# Me-Line_Finder_v2_0.net
KiCad netlist of a schematic drawn in EAGLE
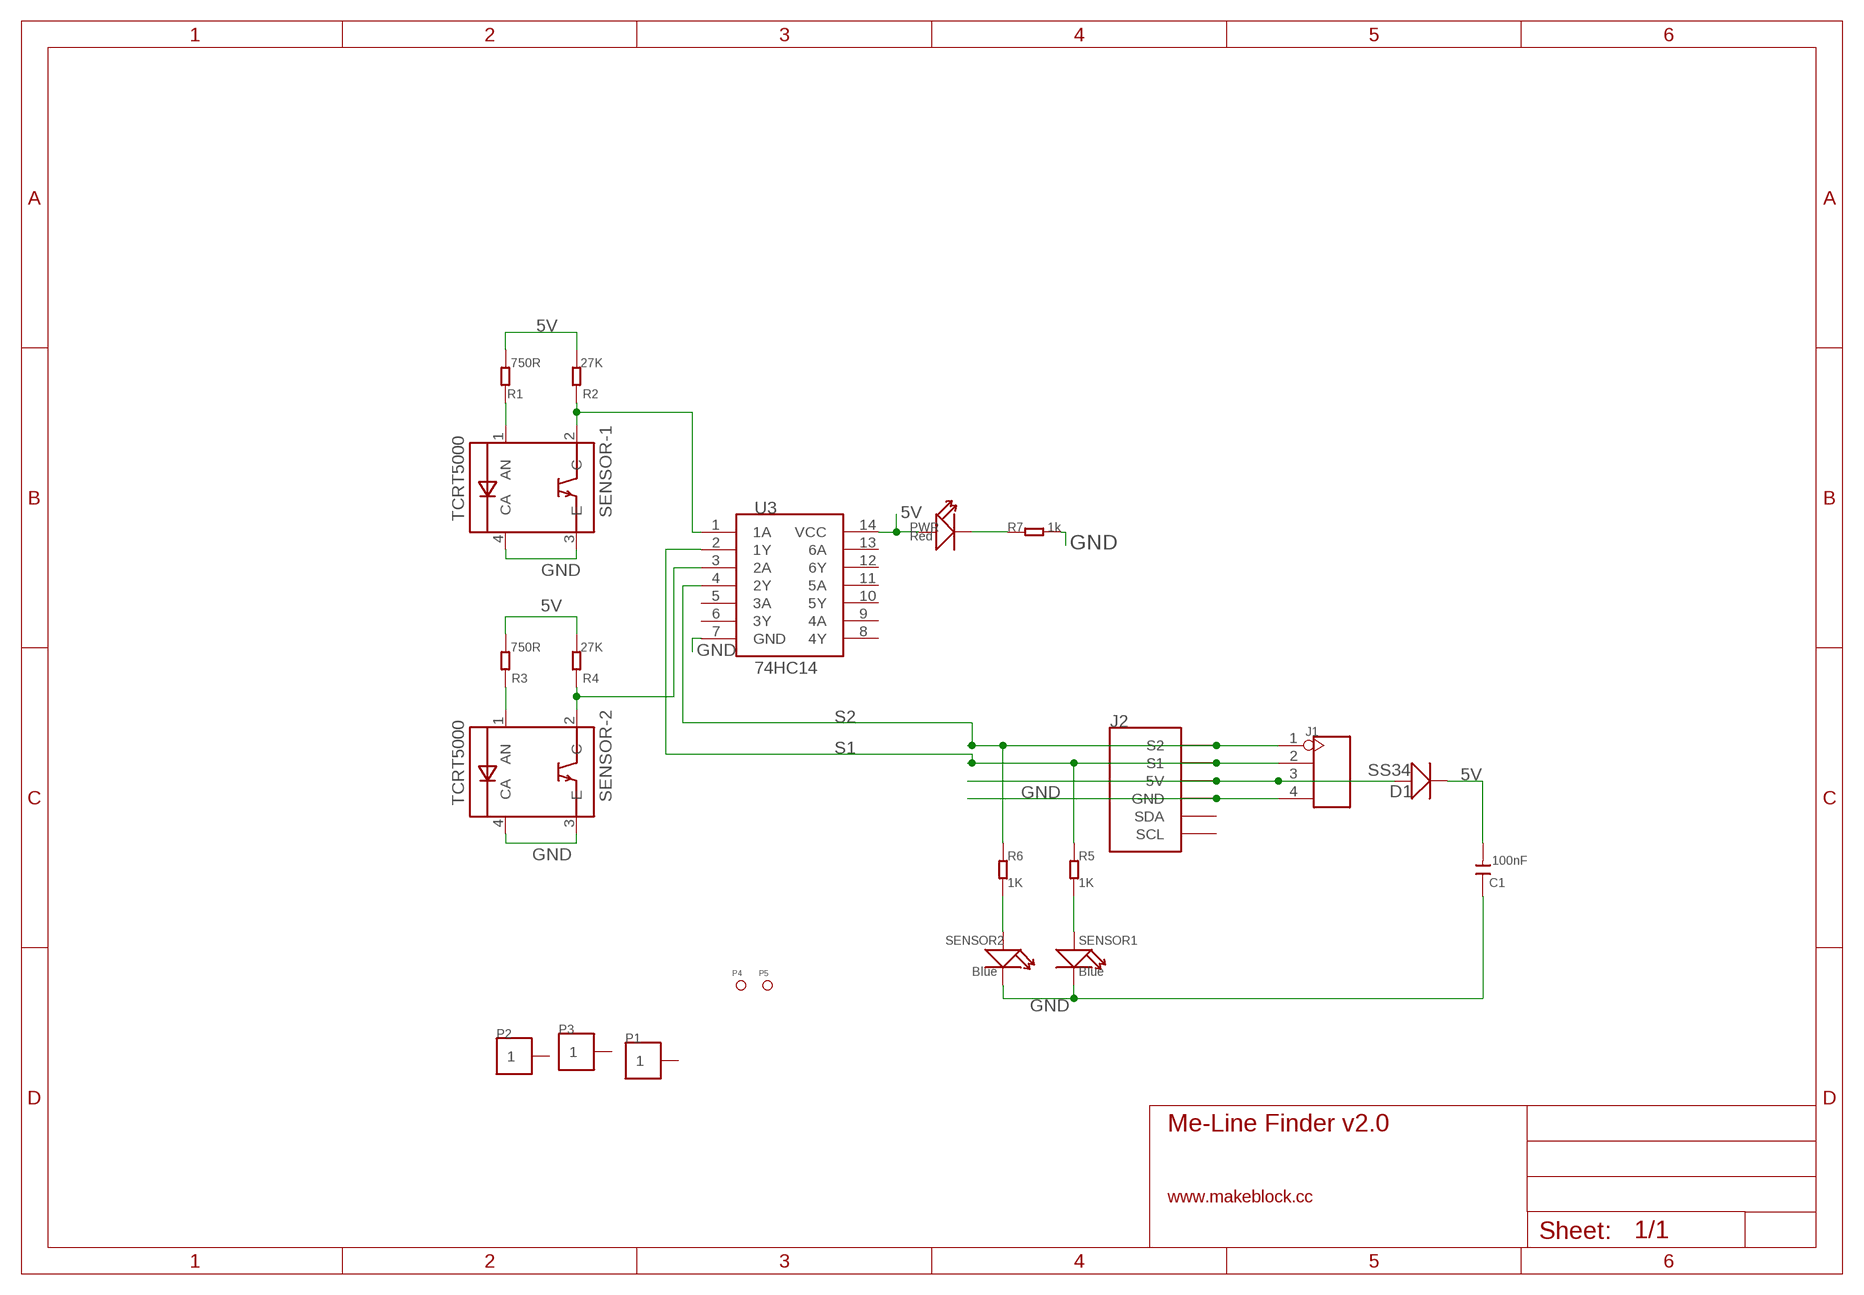
[diagram p0: schematic, sheet 1]

(export (version "E")
  (design (tool "Eeschema 10.0.6"))
  (components
    (comp (ref "C1")
      (value "100nF")
      (footprint "eagle-import:0603")
      (libsource (lib "eagle-import") (part "C-0603"))
    )
    (comp (ref "D1")
      (value "SS34")
      (footprint "eagle-import:D2010")
      (libsource (lib "eagle-import") (part "D'SMA'"))
    )
    (comp (ref "J1")
      (value "HEADER-4P-60/35MIL")
      (footprint "eagle-import:4P-65_35MIL")
      (libsource (lib "eagle-import") (part "HEADER-4P-60/35MIL"))
    )
    (comp (ref "J2")
      (value "RJ11-6P6C-DIGI")
      (footprint "eagle-import:RJ11-6P6C")
      (libsource (lib "eagle-import") (part "RJ11-6P6C-DIGI"))
    )
    (comp (ref "P1")
      (value "PAD-1P-4MM")
      (footprint "eagle-import:HOLE-01")
      (libsource (lib "eagle-import") (part "PAD-1P-4MM"))
    )
    (comp (ref "P2")
      (value "PAD-1P-4MM")
      (footprint "eagle-import:HOLE-01")
      (libsource (lib "eagle-import") (part "PAD-1P-4MM"))
    )
    (comp (ref "P3")
      (value "PAD-1P-4MM")
      (footprint "eagle-import:HOLE-01")
      (libsource (lib "eagle-import") (part "PAD-1P-4MM"))
    )
    (comp (ref "P4")
      (value "PAD-MARK")
      (footprint "eagle-import:ROUND-MARK-1.0")
      (fields (field (name "PARTNO") "DNP"))
      (libsource (lib "eagle-import") (part "PAD-MARK"))
    )
    (comp (ref "P5")
      (value "PAD-MARK")
      (footprint "eagle-import:ROUND-MARK-1.0")
      (fields (field (name "PARTNO") "DNP"))
      (libsource (lib "eagle-import") (part "PAD-MARK"))
    )
    (comp (ref "PWR")
      (value "Red")
      (footprint "eagle-import:LED-0603")
      (libsource (lib "eagle-import") (part "LED'0603'"))
    )
    (comp (ref "R1")
      (value "750R")
      (footprint "eagle-import:0603")
      (libsource (lib "eagle-import") (part "R-0603"))
    )
    (comp (ref "R2")
      (value "27K")
      (footprint "eagle-import:0603")
      (libsource (lib "eagle-import") (part "R-0603"))
    )
    (comp (ref "R3")
      (value "750R")
      (footprint "eagle-import:0603")
      (libsource (lib "eagle-import") (part "R-0603"))
    )
    (comp (ref "R4")
      (value "27K")
      (footprint "eagle-import:0603")
      (libsource (lib "eagle-import") (part "R-0603"))
    )
    (comp (ref "R5")
      (value "1K")
      (footprint "eagle-import:0603")
      (libsource (lib "eagle-import") (part "R-0603"))
    )
    (comp (ref "R6")
      (value "1K")
      (footprint "eagle-import:0603")
      (libsource (lib "eagle-import") (part "R-0603"))
    )
    (comp (ref "R7")
      (value "1k")
      (footprint "eagle-import:0603")
      (libsource (lib "eagle-import") (part "R-0603"))
    )
    (comp (ref "SENSOR-1")
      (value "TCRT5000")
      (footprint "eagle-import:TCRT5000")
      (libsource (lib "eagle-import") (part "TCRT5000"))
    )
    (comp (ref "SENSOR-2")
      (value "TCRT5000")
      (footprint "eagle-import:TCRT5000")
      (libsource (lib "eagle-import") (part "TCRT5000"))
    )
    (comp (ref "SENSOR1")
      (value "Blue")
      (footprint "eagle-import:LED-0603")
      (libsource (lib "eagle-import") (part "LED'0603'"))
    )
    (comp (ref "SENSOR2")
      (value "Blue")
      (footprint "eagle-import:LED-0603")
      (libsource (lib "eagle-import") (part "LED'0603'"))
    )
    (comp (ref "U3")
      (value "74HC14")
      (footprint "eagle-import:TSSOP14")
      (libsource (lib "eagle-import") (part "74HC14"))
    )
  )
  (nets
    (net (code "1") (name "/5V") (class "Default")
      (node (ref "C1") (pin "2") (pinfunction "2_2") (pintype "passive"))
      (node (ref "D1") (pin "-") (pinfunction "-_-") (pintype "passive"))
      (node (ref "PWR") (pin "+") (pinfunction "+_+") (pintype "passive"))
      (node (ref "R1") (pin "2") (pinfunction "2_2") (pintype "passive"))
      (node (ref "R2") (pin "2") (pinfunction "2_2") (pintype "passive"))
      (node (ref "R3") (pin "2") (pinfunction "2_2") (pintype "passive"))
      (node (ref "R4") (pin "2") (pinfunction "2_2") (pintype "passive"))
      (node (ref "U3") (pin "14") (pinfunction "VCC_14") (pintype "bidirectional"))
    )
    (net (code "2") (name "/GND") (class "Default")
      (node (ref "C1") (pin "1") (pinfunction "1_1") (pintype "passive"))
      (node (ref "J1") (pin "4") (pinfunction "P$4_4") (pintype "bidirectional"))
      (node (ref "J2") (pin "3") (pinfunction "GND_3") (pintype "bidirectional"))
      (node (ref "R7") (pin "2") (pinfunction "2_2") (pintype "passive"))
      (node (ref "SENSOR-1") (pin "3") (pinfunction "E_3") (pintype "bidirectional"))
      (node (ref "SENSOR-1") (pin "4") (pinfunction "CA_4") (pintype "bidirectional"))
      (node (ref "SENSOR-2") (pin "3") (pinfunction "E_3") (pintype "bidirectional"))
      (node (ref "SENSOR-2") (pin "4") (pinfunction "CA_4") (pintype "bidirectional"))
      (node (ref "SENSOR1") (pin "-") (pinfunction "-_-") (pintype "passive"))
      (node (ref "SENSOR2") (pin "-") (pinfunction "-_-") (pintype "passive"))
      (node (ref "U3") (pin "7") (pinfunction "GND_7") (pintype "bidirectional"))
    )
    (net (code "3") (name "/S1") (class "Default")
      (node (ref "J1") (pin "2") (pinfunction "P$2_2") (pintype "bidirectional"))
      (node (ref "J2") (pin "5") (pinfunction "S1_5") (pintype "bidirectional"))
      (node (ref "R5") (pin "1") (pinfunction "1_1") (pintype "passive"))
      (node (ref "U3") (pin "2") (pinfunction "1Y_2") (pintype "bidirectional"))
    )
    (net (code "4") (name "/S2") (class "Default")
      (node (ref "J1") (pin "1") (pinfunction "P$1_1") (pintype "bidirectional"))
      (node (ref "J2") (pin "6") (pinfunction "S2_6") (pintype "bidirectional"))
      (node (ref "R6") (pin "1") (pinfunction "1_1") (pintype "passive"))
      (node (ref "U3") (pin "4") (pinfunction "2Y_4") (pintype "bidirectional"))
    )
    (net (code "5") (name "Net-(J1-P$3)") (class "Default")
      (node (ref "D1") (pin "+") (pinfunction "+_+") (pintype "passive"))
      (node (ref "J1") (pin "3") (pinfunction "P$3_3") (pintype "bidirectional"))
      (node (ref "J2") (pin "4") (pinfunction "5V_4") (pintype "bidirectional"))
    )
    (net (code "6") (name "Net-(PWR-Pad-)") (class "Default")
      (node (ref "PWR") (pin "-") (pinfunction "-_-") (pintype "passive"))
      (node (ref "R7") (pin "1") (pinfunction "1_1") (pintype "passive"))
    )
    (net (code "7") (name "Net-(R5-Pad2)") (class "Default")
      (node (ref "R5") (pin "2") (pinfunction "2_2") (pintype "passive"))
      (node (ref "SENSOR1") (pin "+") (pinfunction "+_+") (pintype "passive"))
    )
    (net (code "8") (name "Net-(R6-Pad2)") (class "Default")
      (node (ref "R6") (pin "2") (pinfunction "2_2") (pintype "passive"))
      (node (ref "SENSOR2") (pin "+") (pinfunction "+_+") (pintype "passive"))
    )
    (net (code "9") (name "Net-(SENSOR-1-AN)") (class "Default")
      (node (ref "R1") (pin "1") (pinfunction "1_1") (pintype "passive"))
      (node (ref "SENSOR-1") (pin "1") (pinfunction "AN_1") (pintype "bidirectional"))
    )
    (net (code "10") (name "Net-(SENSOR-1-C)") (class "Default")
      (node (ref "R2") (pin "1") (pinfunction "1_1") (pintype "passive"))
      (node (ref "SENSOR-1") (pin "2") (pinfunction "C_2") (pintype "bidirectional"))
      (node (ref "U3") (pin "1") (pinfunction "1A_1") (pintype "bidirectional"))
    )
    (net (code "11") (name "Net-(SENSOR-2-AN)") (class "Default")
      (node (ref "R3") (pin "1") (pinfunction "1_1") (pintype "passive"))
      (node (ref "SENSOR-2") (pin "1") (pinfunction "AN_1") (pintype "bidirectional"))
    )
    (net (code "12") (name "Net-(SENSOR-2-C)") (class "Default")
      (node (ref "R4") (pin "1") (pinfunction "1_1") (pintype "passive"))
      (node (ref "SENSOR-2") (pin "2") (pinfunction "C_2") (pintype "bidirectional"))
      (node (ref "U3") (pin "3") (pinfunction "2A_3") (pintype "bidirectional"))
    )
    (net (code "13") (name "unconnected-(J2-SCL-Pad1)") (class "Default")
      (node (ref "J2") (pin "1") (pinfunction "SCL_1") (pintype "bidirectional"))
    )
    (net (code "14") (name "unconnected-(J2-SDA-Pad2)") (class "Default")
      (node (ref "J2") (pin "2") (pinfunction "SDA_2") (pintype "bidirectional"))
    )
    (net (code "15") (name "unconnected-(P1-Pad1)") (class "Default")
      (node (ref "P1") (pin "1") (pinfunction "1_1") (pintype "bidirectional"))
    )
    (net (code "16") (name "unconnected-(P2-Pad1)") (class "Default")
      (node (ref "P2") (pin "1") (pinfunction "1_1") (pintype "bidirectional"))
    )
    (net (code "17") (name "unconnected-(P3-Pad1)") (class "Default")
      (node (ref "P3") (pin "1") (pinfunction "1_1") (pintype "bidirectional"))
    )
    (net (code "18") (name "unconnected-(U3-3A-Pad5)") (class "Default")
      (node (ref "U3") (pin "5") (pinfunction "3A_5") (pintype "bidirectional"))
    )
    (net (code "19") (name "unconnected-(U3-3Y-Pad6)") (class "Default")
      (node (ref "U3") (pin "6") (pinfunction "3Y_6") (pintype "bidirectional"))
    )
    (net (code "20") (name "unconnected-(U3-4A-Pad9)") (class "Default")
      (node (ref "U3") (pin "9") (pinfunction "4A_9") (pintype "bidirectional"))
    )
    (net (code "21") (name "unconnected-(U3-4Y-Pad8)") (class "Default")
      (node (ref "U3") (pin "8") (pinfunction "4Y_8") (pintype "bidirectional"))
    )
    (net (code "22") (name "unconnected-(U3-5A-Pad11)") (class "Default")
      (node (ref "U3") (pin "11") (pinfunction "5A_11") (pintype "bidirectional"))
    )
    (net (code "23") (name "unconnected-(U3-5Y-Pad10)") (class "Default")
      (node (ref "U3") (pin "10") (pinfunction "5Y_10") (pintype "bidirectional"))
    )
    (net (code "24") (name "unconnected-(U3-6A-Pad13)") (class "Default")
      (node (ref "U3") (pin "13") (pinfunction "6A_13") (pintype "bidirectional"))
    )
    (net (code "25") (name "unconnected-(U3-6Y-Pad12)") (class "Default")
      (node (ref "U3") (pin "12") (pinfunction "6Y_12") (pintype "bidirectional"))
    )
  )
)
